# LEDBoard.net
KiCad netlist of a schematic drawn in EAGLE
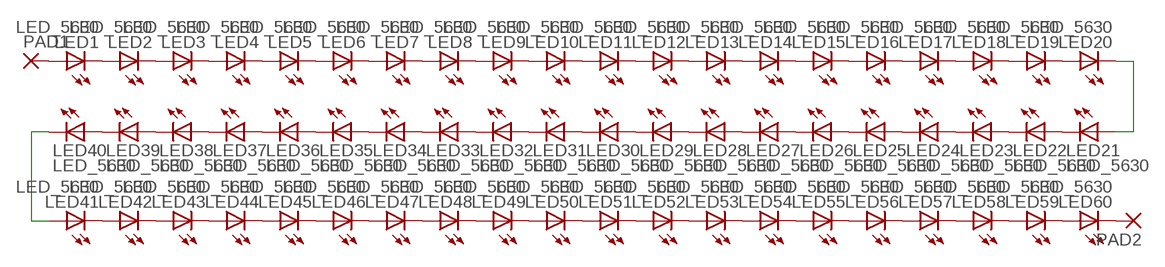
[diagram p0: schematic, sheet 1]

(export (version "E")
  (design (tool "Eeschema 10.0.6"))
  (components
    (comp (ref "LED1")
      (value "LED_5630")
      (footprint "eagle-import:LED5730")
      (libsource (lib "eagle-import") (part "LED_5630"))
    )
    (comp (ref "LED2")
      (value "LED_5630")
      (footprint "eagle-import:LED5730")
      (libsource (lib "eagle-import") (part "LED_5630"))
    )
    (comp (ref "LED3")
      (value "LED_5630")
      (footprint "eagle-import:LED5730")
      (libsource (lib "eagle-import") (part "LED_5630"))
    )
    (comp (ref "LED4")
      (value "LED_5630")
      (footprint "eagle-import:LED5730")
      (libsource (lib "eagle-import") (part "LED_5630"))
    )
    (comp (ref "LED5")
      (value "LED_5630")
      (footprint "eagle-import:LED5730")
      (libsource (lib "eagle-import") (part "LED_5630"))
    )
    (comp (ref "LED6")
      (value "LED_5630")
      (footprint "eagle-import:LED5730")
      (libsource (lib "eagle-import") (part "LED_5630"))
    )
    (comp (ref "LED7")
      (value "LED_5630")
      (footprint "eagle-import:LED5730")
      (libsource (lib "eagle-import") (part "LED_5630"))
    )
    (comp (ref "LED8")
      (value "LED_5630")
      (footprint "eagle-import:LED5730")
      (libsource (lib "eagle-import") (part "LED_5630"))
    )
    (comp (ref "LED9")
      (value "LED_5630")
      (footprint "eagle-import:LED5730")
      (libsource (lib "eagle-import") (part "LED_5630"))
    )
    (comp (ref "LED10")
      (value "LED_5630")
      (footprint "eagle-import:LED5730")
      (libsource (lib "eagle-import") (part "LED_5630"))
    )
    (comp (ref "LED11")
      (value "LED_5630")
      (footprint "eagle-import:LED5730")
      (libsource (lib "eagle-import") (part "LED_5630"))
    )
    (comp (ref "LED12")
      (value "LED_5630")
      (footprint "eagle-import:LED5730")
      (libsource (lib "eagle-import") (part "LED_5630"))
    )
    (comp (ref "LED13")
      (value "LED_5630")
      (footprint "eagle-import:LED5730")
      (libsource (lib "eagle-import") (part "LED_5630"))
    )
    (comp (ref "LED14")
      (value "LED_5630")
      (footprint "eagle-import:LED5730")
      (libsource (lib "eagle-import") (part "LED_5630"))
    )
    (comp (ref "LED15")
      (value "LED_5630")
      (footprint "eagle-import:LED5730")
      (libsource (lib "eagle-import") (part "LED_5630"))
    )
    (comp (ref "LED16")
      (value "LED_5630")
      (footprint "eagle-import:LED5730")
      (libsource (lib "eagle-import") (part "LED_5630"))
    )
    (comp (ref "LED17")
      (value "LED_5630")
      (footprint "eagle-import:LED5730")
      (libsource (lib "eagle-import") (part "LED_5630"))
    )
    (comp (ref "LED18")
      (value "LED_5630")
      (footprint "eagle-import:LED5730")
      (libsource (lib "eagle-import") (part "LED_5630"))
    )
    (comp (ref "LED19")
      (value "LED_5630")
      (footprint "eagle-import:LED5730")
      (libsource (lib "eagle-import") (part "LED_5630"))
    )
    (comp (ref "LED20")
      (value "LED_5630")
      (footprint "eagle-import:LED5730")
      (libsource (lib "eagle-import") (part "LED_5630"))
    )
    (comp (ref "LED21")
      (value "LED_5630")
      (footprint "eagle-import:LED5730")
      (libsource (lib "eagle-import") (part "LED_5630"))
    )
    (comp (ref "LED22")
      (value "LED_5630")
      (footprint "eagle-import:LED5730")
      (libsource (lib "eagle-import") (part "LED_5630"))
    )
    (comp (ref "LED23")
      (value "LED_5630")
      (footprint "eagle-import:LED5730")
      (libsource (lib "eagle-import") (part "LED_5630"))
    )
    (comp (ref "LED24")
      (value "LED_5630")
      (footprint "eagle-import:LED5730")
      (libsource (lib "eagle-import") (part "LED_5630"))
    )
    (comp (ref "LED25")
      (value "LED_5630")
      (footprint "eagle-import:LED5730")
      (libsource (lib "eagle-import") (part "LED_5630"))
    )
    (comp (ref "LED26")
      (value "LED_5630")
      (footprint "eagle-import:LED5730")
      (libsource (lib "eagle-import") (part "LED_5630"))
    )
    (comp (ref "LED27")
      (value "LED_5630")
      (footprint "eagle-import:LED5730")
      (libsource (lib "eagle-import") (part "LED_5630"))
    )
    (comp (ref "LED28")
      (value "LED_5630")
      (footprint "eagle-import:LED5730")
      (libsource (lib "eagle-import") (part "LED_5630"))
    )
    (comp (ref "LED29")
      (value "LED_5630")
      (footprint "eagle-import:LED5730")
      (libsource (lib "eagle-import") (part "LED_5630"))
    )
    (comp (ref "LED30")
      (value "LED_5630")
      (footprint "eagle-import:LED5730")
      (libsource (lib "eagle-import") (part "LED_5630"))
    )
    (comp (ref "LED31")
      (value "LED_5630")
      (footprint "eagle-import:LED5730")
      (libsource (lib "eagle-import") (part "LED_5630"))
    )
    (comp (ref "LED32")
      (value "LED_5630")
      (footprint "eagle-import:LED5730")
      (libsource (lib "eagle-import") (part "LED_5630"))
    )
    (comp (ref "LED33")
      (value "LED_5630")
      (footprint "eagle-import:LED5730")
      (libsource (lib "eagle-import") (part "LED_5630"))
    )
    (comp (ref "LED34")
      (value "LED_5630")
      (footprint "eagle-import:LED5730")
      (libsource (lib "eagle-import") (part "LED_5630"))
    )
    (comp (ref "LED35")
      (value "LED_5630")
      (footprint "eagle-import:LED5730")
      (libsource (lib "eagle-import") (part "LED_5630"))
    )
    (comp (ref "LED36")
      (value "LED_5630")
      (footprint "eagle-import:LED5730")
      (libsource (lib "eagle-import") (part "LED_5630"))
    )
    (comp (ref "LED37")
      (value "LED_5630")
      (footprint "eagle-import:LED5730")
      (libsource (lib "eagle-import") (part "LED_5630"))
    )
    (comp (ref "LED38")
      (value "LED_5630")
      (footprint "eagle-import:LED5730")
      (libsource (lib "eagle-import") (part "LED_5630"))
    )
    (comp (ref "LED39")
      (value "LED_5630")
      (footprint "eagle-import:LED5730")
      (libsource (lib "eagle-import") (part "LED_5630"))
    )
    (comp (ref "LED40")
      (value "LED_5630")
      (footprint "eagle-import:LED5730")
      (libsource (lib "eagle-import") (part "LED_5630"))
    )
    (comp (ref "LED41")
      (value "LED_5630")
      (footprint "eagle-import:LED5730")
      (libsource (lib "eagle-import") (part "LED_5630"))
    )
    (comp (ref "LED42")
      (value "LED_5630")
      (footprint "eagle-import:LED5730")
      (libsource (lib "eagle-import") (part "LED_5630"))
    )
    (comp (ref "LED43")
      (value "LED_5630")
      (footprint "eagle-import:LED5730")
      (libsource (lib "eagle-import") (part "LED_5630"))
    )
    (comp (ref "LED44")
      (value "LED_5630")
      (footprint "eagle-import:LED5730")
      (libsource (lib "eagle-import") (part "LED_5630"))
    )
    (comp (ref "LED45")
      (value "LED_5630")
      (footprint "eagle-import:LED5730")
      (libsource (lib "eagle-import") (part "LED_5630"))
    )
    (comp (ref "LED46")
      (value "LED_5630")
      (footprint "eagle-import:LED5730")
      (libsource (lib "eagle-import") (part "LED_5630"))
    )
    (comp (ref "LED47")
      (value "LED_5630")
      (footprint "eagle-import:LED5730")
      (libsource (lib "eagle-import") (part "LED_5630"))
    )
    (comp (ref "LED48")
      (value "LED_5630")
      (footprint "eagle-import:LED5730")
      (libsource (lib "eagle-import") (part "LED_5630"))
    )
    (comp (ref "LED49")
      (value "LED_5630")
      (footprint "eagle-import:LED5730")
      (libsource (lib "eagle-import") (part "LED_5630"))
    )
    (comp (ref "LED50")
      (value "LED_5630")
      (footprint "eagle-import:LED5730")
      (libsource (lib "eagle-import") (part "LED_5630"))
    )
    (comp (ref "LED51")
      (value "LED_5630")
      (footprint "eagle-import:LED5730")
      (libsource (lib "eagle-import") (part "LED_5630"))
    )
    (comp (ref "LED52")
      (value "LED_5630")
      (footprint "eagle-import:LED5730")
      (libsource (lib "eagle-import") (part "LED_5630"))
    )
    (comp (ref "LED53")
      (value "LED_5630")
      (footprint "eagle-import:LED5730")
      (libsource (lib "eagle-import") (part "LED_5630"))
    )
    (comp (ref "LED54")
      (value "LED_5630")
      (footprint "eagle-import:LED5730")
      (libsource (lib "eagle-import") (part "LED_5630"))
    )
    (comp (ref "LED55")
      (value "LED_5630")
      (footprint "eagle-import:LED5730")
      (libsource (lib "eagle-import") (part "LED_5630"))
    )
    (comp (ref "LED56")
      (value "LED_5630")
      (footprint "eagle-import:LED5730")
      (libsource (lib "eagle-import") (part "LED_5630"))
    )
    (comp (ref "LED57")
      (value "LED_5630")
      (footprint "eagle-import:LED5730")
      (libsource (lib "eagle-import") (part "LED_5630"))
    )
    (comp (ref "LED58")
      (value "LED_5630")
      (footprint "eagle-import:LED5730")
      (libsource (lib "eagle-import") (part "LED_5630"))
    )
    (comp (ref "LED59")
      (value "LED_5630")
      (footprint "eagle-import:LED5730")
      (libsource (lib "eagle-import") (part "LED_5630"))
    )
    (comp (ref "LED60")
      (value "LED_5630")
      (footprint "eagle-import:LED5730")
      (libsource (lib "eagle-import") (part "LED_5630"))
    )
    (comp (ref "PAD1")
      (value "SMD5")
      (footprint "eagle-import:SMD2,54-5,08")
      (libsource (lib "eagle-import") (part "SMD5"))
    )
    (comp (ref "PAD2")
      (value "SMD5")
      (footprint "eagle-import:SMD2,54-5,08")
      (libsource (lib "eagle-import") (part "SMD5"))
    )
  )
  (nets
    (net (code "1") (name "Net-(LED1-PadC)") (class "Default")
      (node (ref "LED1") (pin "C") (pinfunction "C_C") (pintype "passive"))
      (node (ref "LED2") (pin "A") (pinfunction "A_A") (pintype "passive"))
      (node (ref "LED2") (pin "A1") (pinfunction "A_A1") (pintype "passive"))
    )
    (net (code "2") (name "Net-(LED2-PadC)") (class "Default")
      (node (ref "LED2") (pin "C") (pinfunction "C_C") (pintype "passive"))
      (node (ref "LED3") (pin "A") (pinfunction "A_A") (pintype "passive"))
      (node (ref "LED3") (pin "A1") (pinfunction "A_A1") (pintype "passive"))
    )
    (net (code "3") (name "Net-(LED3-PadC)") (class "Default")
      (node (ref "LED3") (pin "C") (pinfunction "C_C") (pintype "passive"))
      (node (ref "LED4") (pin "A") (pinfunction "A_A") (pintype "passive"))
      (node (ref "LED4") (pin "A1") (pinfunction "A_A1") (pintype "passive"))
    )
    (net (code "4") (name "Net-(LED4-PadC)") (class "Default")
      (node (ref "LED4") (pin "C") (pinfunction "C_C") (pintype "passive"))
      (node (ref "LED5") (pin "A") (pinfunction "A_A") (pintype "passive"))
      (node (ref "LED5") (pin "A1") (pinfunction "A_A1") (pintype "passive"))
    )
    (net (code "5") (name "Net-(LED5-PadC)") (class "Default")
      (node (ref "LED5") (pin "C") (pinfunction "C_C") (pintype "passive"))
      (node (ref "LED6") (pin "A") (pinfunction "A_A") (pintype "passive"))
      (node (ref "LED6") (pin "A1") (pinfunction "A_A1") (pintype "passive"))
    )
    (net (code "6") (name "Net-(LED6-PadC)") (class "Default")
      (node (ref "LED6") (pin "C") (pinfunction "C_C") (pintype "passive"))
      (node (ref "LED7") (pin "A") (pinfunction "A_A") (pintype "passive"))
      (node (ref "LED7") (pin "A1") (pinfunction "A_A1") (pintype "passive"))
    )
    (net (code "7") (name "Net-(LED7-PadC)") (class "Default")
      (node (ref "LED7") (pin "C") (pinfunction "C_C") (pintype "passive"))
      (node (ref "LED8") (pin "A") (pinfunction "A_A") (pintype "passive"))
      (node (ref "LED8") (pin "A1") (pinfunction "A_A1") (pintype "passive"))
    )
    (net (code "8") (name "Net-(LED8-PadC)") (class "Default")
      (node (ref "LED8") (pin "C") (pinfunction "C_C") (pintype "passive"))
      (node (ref "LED9") (pin "A") (pinfunction "A_A") (pintype "passive"))
      (node (ref "LED9") (pin "A1") (pinfunction "A_A1") (pintype "passive"))
    )
    (net (code "9") (name "Net-(LED10-A-PadA1)") (class "Default")
      (node (ref "LED10") (pin "A") (pinfunction "A_A") (pintype "passive"))
      (node (ref "LED10") (pin "A1") (pinfunction "A_A1") (pintype "passive"))
      (node (ref "LED9") (pin "C") (pinfunction "C_C") (pintype "passive"))
    )
    (net (code "10") (name "Net-(LED10-PadC)") (class "Default")
      (node (ref "LED10") (pin "C") (pinfunction "C_C") (pintype "passive"))
      (node (ref "LED11") (pin "A") (pinfunction "A_A") (pintype "passive"))
      (node (ref "LED11") (pin "A1") (pinfunction "A_A1") (pintype "passive"))
    )
    (net (code "11") (name "Net-(LED11-PadC)") (class "Default")
      (node (ref "LED11") (pin "C") (pinfunction "C_C") (pintype "passive"))
      (node (ref "LED12") (pin "A") (pinfunction "A_A") (pintype "passive"))
      (node (ref "LED12") (pin "A1") (pinfunction "A_A1") (pintype "passive"))
    )
    (net (code "12") (name "Net-(LED12-PadC)") (class "Default")
      (node (ref "LED12") (pin "C") (pinfunction "C_C") (pintype "passive"))
      (node (ref "LED13") (pin "A") (pinfunction "A_A") (pintype "passive"))
      (node (ref "LED13") (pin "A1") (pinfunction "A_A1") (pintype "passive"))
    )
    (net (code "13") (name "Net-(LED13-PadC)") (class "Default")
      (node (ref "LED13") (pin "C") (pinfunction "C_C") (pintype "passive"))
      (node (ref "LED14") (pin "A") (pinfunction "A_A") (pintype "passive"))
      (node (ref "LED14") (pin "A1") (pinfunction "A_A1") (pintype "passive"))
    )
    (net (code "14") (name "Net-(LED14-PadC)") (class "Default")
      (node (ref "LED14") (pin "C") (pinfunction "C_C") (pintype "passive"))
      (node (ref "LED15") (pin "A") (pinfunction "A_A") (pintype "passive"))
      (node (ref "LED15") (pin "A1") (pinfunction "A_A1") (pintype "passive"))
    )
    (net (code "15") (name "Net-(LED15-PadC)") (class "Default")
      (node (ref "LED15") (pin "C") (pinfunction "C_C") (pintype "passive"))
      (node (ref "LED16") (pin "A") (pinfunction "A_A") (pintype "passive"))
      (node (ref "LED16") (pin "A1") (pinfunction "A_A1") (pintype "passive"))
    )
    (net (code "16") (name "Net-(LED16-PadC)") (class "Default")
      (node (ref "LED16") (pin "C") (pinfunction "C_C") (pintype "passive"))
      (node (ref "LED17") (pin "A") (pinfunction "A_A") (pintype "passive"))
      (node (ref "LED17") (pin "A1") (pinfunction "A_A1") (pintype "passive"))
    )
    (net (code "17") (name "Net-(LED17-PadC)") (class "Default")
      (node (ref "LED17") (pin "C") (pinfunction "C_C") (pintype "passive"))
      (node (ref "LED18") (pin "A") (pinfunction "A_A") (pintype "passive"))
      (node (ref "LED18") (pin "A1") (pinfunction "A_A1") (pintype "passive"))
    )
    (net (code "18") (name "Net-(LED18-PadC)") (class "Default")
      (node (ref "LED18") (pin "C") (pinfunction "C_C") (pintype "passive"))
      (node (ref "LED19") (pin "A") (pinfunction "A_A") (pintype "passive"))
      (node (ref "LED19") (pin "A1") (pinfunction "A_A1") (pintype "passive"))
    )
    (net (code "19") (name "Net-(LED19-PadC)") (class "Default")
      (node (ref "LED19") (pin "C") (pinfunction "C_C") (pintype "passive"))
      (node (ref "LED20") (pin "A") (pinfunction "A_A") (pintype "passive"))
      (node (ref "LED20") (pin "A1") (pinfunction "A_A1") (pintype "passive"))
    )
    (net (code "20") (name "Net-(LED20-PadC)") (class "Default")
      (node (ref "LED20") (pin "C") (pinfunction "C_C") (pintype "passive"))
      (node (ref "LED21") (pin "A") (pinfunction "A_A") (pintype "passive"))
      (node (ref "LED21") (pin "A1") (pinfunction "A_A1") (pintype "passive"))
    )
    (net (code "21") (name "Net-(LED21-PadC)") (class "Default")
      (node (ref "LED21") (pin "C") (pinfunction "C_C") (pintype "passive"))
      (node (ref "LED22") (pin "A") (pinfunction "A_A") (pintype "passive"))
      (node (ref "LED22") (pin "A1") (pinfunction "A_A1") (pintype "passive"))
    )
    (net (code "22") (name "Net-(LED22-PadC)") (class "Default")
      (node (ref "LED22") (pin "C") (pinfunction "C_C") (pintype "passive"))
      (node (ref "LED23") (pin "A") (pinfunction "A_A") (pintype "passive"))
      (node (ref "LED23") (pin "A1") (pinfunction "A_A1") (pintype "passive"))
    )
    (net (code "23") (name "Net-(LED23-PadC)") (class "Default")
      (node (ref "LED23") (pin "C") (pinfunction "C_C") (pintype "passive"))
      (node (ref "LED24") (pin "A") (pinfunction "A_A") (pintype "passive"))
      (node (ref "LED24") (pin "A1") (pinfunction "A_A1") (pintype "passive"))
    )
    (net (code "24") (name "Net-(LED24-PadC)") (class "Default")
      (node (ref "LED24") (pin "C") (pinfunction "C_C") (pintype "passive"))
      (node (ref "LED25") (pin "A") (pinfunction "A_A") (pintype "passive"))
      (node (ref "LED25") (pin "A1") (pinfunction "A_A1") (pintype "passive"))
    )
    (net (code "25") (name "Net-(LED25-PadC)") (class "Default")
      (node (ref "LED25") (pin "C") (pinfunction "C_C") (pintype "passive"))
      (node (ref "LED26") (pin "A") (pinfunction "A_A") (pintype "passive"))
      (node (ref "LED26") (pin "A1") (pinfunction "A_A1") (pintype "passive"))
    )
    (net (code "26") (name "Net-(LED26-PadC)") (class "Default")
      (node (ref "LED26") (pin "C") (pinfunction "C_C") (pintype "passive"))
      (node (ref "LED27") (pin "A") (pinfunction "A_A") (pintype "passive"))
      (node (ref "LED27") (pin "A1") (pinfunction "A_A1") (pintype "passive"))
    )
    (net (code "27") (name "Net-(LED27-PadC)") (class "Default")
      (node (ref "LED27") (pin "C") (pinfunction "C_C") (pintype "passive"))
      (node (ref "LED28") (pin "A") (pinfunction "A_A") (pintype "passive"))
      (node (ref "LED28") (pin "A1") (pinfunction "A_A1") (pintype "passive"))
    )
    (net (code "28") (name "Net-(LED28-PadC)") (class "Default")
      (node (ref "LED28") (pin "C") (pinfunction "C_C") (pintype "passive"))
      (node (ref "LED29") (pin "A") (pinfunction "A_A") (pintype "passive"))
      (node (ref "LED29") (pin "A1") (pinfunction "A_A1") (pintype "passive"))
    )
    (net (code "29") (name "Net-(LED29-PadC)") (class "Default")
      (node (ref "LED29") (pin "C") (pinfunction "C_C") (pintype "passive"))
      (node (ref "LED30") (pin "A") (pinfunction "A_A") (pintype "passive"))
      (node (ref "LED30") (pin "A1") (pinfunction "A_A1") (pintype "passive"))
    )
    (net (code "30") (name "Net-(LED30-PadC)") (class "Default")
      (node (ref "LED30") (pin "C") (pinfunction "C_C") (pintype "passive"))
      (node (ref "LED31") (pin "A") (pinfunction "A_A") (pintype "passive"))
      (node (ref "LED31") (pin "A1") (pinfunction "A_A1") (pintype "passive"))
    )
    (net (code "31") (name "Net-(LED31-PadC)") (class "Default")
      (node (ref "LED31") (pin "C") (pinfunction "C_C") (pintype "passive"))
      (node (ref "LED32") (pin "A") (pinfunction "A_A") (pintype "passive"))
      (node (ref "LED32") (pin "A1") (pinfunction "A_A1") (pintype "passive"))
    )
    (net (code "32") (name "Net-(LED32-PadC)") (class "Default")
      (node (ref "LED32") (pin "C") (pinfunction "C_C") (pintype "passive"))
      (node (ref "LED33") (pin "A") (pinfunction "A_A") (pintype "passive"))
      (node (ref "LED33") (pin "A1") (pinfunction "A_A1") (pintype "passive"))
    )
    (net (code "33") (name "Net-(LED33-PadC)") (class "Default")
      (node (ref "LED33") (pin "C") (pinfunction "C_C") (pintype "passive"))
      (node (ref "LED34") (pin "A") (pinfunction "A_A") (pintype "passive"))
      (node (ref "LED34") (pin "A1") (pinfunction "A_A1") (pintype "passive"))
    )
    (net (code "34") (name "Net-(LED34-PadC)") (class "Default")
      (node (ref "LED34") (pin "C") (pinfunction "C_C") (pintype "passive"))
      (node (ref "LED35") (pin "A") (pinfunction "A_A") (pintype "passive"))
      (node (ref "LED35") (pin "A1") (pinfunction "A_A1") (pintype "passive"))
    )
    (net (code "35") (name "Net-(LED35-PadC)") (class "Default")
      (node (ref "LED35") (pin "C") (pinfunction "C_C") (pintype "passive"))
      (node (ref "LED36") (pin "A") (pinfunction "A_A") (pintype "passive"))
      (node (ref "LED36") (pin "A1") (pinfunction "A_A1") (pintype "passive"))
    )
    (net (code "36") (name "Net-(LED36-PadC)") (class "Default")
      (node (ref "LED36") (pin "C") (pinfunction "C_C") (pintype "passive"))
      (node (ref "LED37") (pin "A") (pinfunction "A_A") (pintype "passive"))
      (node (ref "LED37") (pin "A1") (pinfunction "A_A1") (pintype "passive"))
    )
    (net (code "37") (name "Net-(LED37-PadC)") (class "Default")
      (node (ref "LED37") (pin "C") (pinfunction "C_C") (pintype "passive"))
      (node (ref "LED38") (pin "A") (pinfunction "A_A") (pintype "passive"))
      (node (ref "LED38") (pin "A1") (pinfunction "A_A1") (pintype "passive"))
    )
    (net (code "38") (name "Net-(LED38-PadC)") (class "Default")
      (node (ref "LED38") (pin "C") (pinfunction "C_C") (pintype "passive"))
      (node (ref "LED39") (pin "A") (pinfunction "A_A") (pintype "passive"))
      (node (ref "LED39") (pin "A1") (pinfunction "A_A1") (pintype "passive"))
    )
    (net (code "39") (name "Net-(LED39-PadC)") (class "Default")
      (node (ref "LED39") (pin "C") (pinfunction "C_C") (pintype "passive"))
      (node (ref "LED40") (pin "A") (pinfunction "A_A") (pintype "passive"))
      (node (ref "LED40") (pin "A1") (pinfunction "A_A1") (pintype "passive"))
    )
    (net (code "40") (name "Net-(LED40-PadC)") (class "Default")
      (node (ref "LED40") (pin "C") (pinfunction "C_C") (pintype "passive"))
      (node (ref "LED41") (pin "A") (pinfunction "A_A") (pintype "passive"))
      (node (ref "LED41") (pin "A1") (pinfunction "A_A1") (pintype "passive"))
    )
    (net (code "41") (name "Net-(LED41-PadC)") (class "Default")
      (node (ref "LED41") (pin "C") (pinfunction "C_C") (pintype "passive"))
      (node (ref "LED42") (pin "A") (pinfunction "A_A") (pintype "passive"))
      (node (ref "LED42") (pin "A1") (pinfunction "A_A1") (pintype "passive"))
    )
    (net (code "42") (name "Net-(LED42-PadC)") (class "Default")
      (node (ref "LED42") (pin "C") (pinfunction "C_C") (pintype "passive"))
      (node (ref "LED43") (pin "A") (pinfunction "A_A") (pintype "passive"))
      (node (ref "LED43") (pin "A1") (pinfunction "A_A1") (pintype "passive"))
    )
    (net (code "43") (name "Net-(LED43-PadC)") (class "Default")
      (node (ref "LED43") (pin "C") (pinfunction "C_C") (pintype "passive"))
      (node (ref "LED44") (pin "A") (pinfunction "A_A") (pintype "passive"))
      (node (ref "LED44") (pin "A1") (pinfunction "A_A1") (pintype "passive"))
    )
    (net (code "44") (name "Net-(LED44-PadC)") (class "Default")
      (node (ref "LED44") (pin "C") (pinfunction "C_C") (pintype "passive"))
      (node (ref "LED45") (pin "A") (pinfunction "A_A") (pintype "passive"))
      (node (ref "LED45") (pin "A1") (pinfunction "A_A1") (pintype "passive"))
    )
    (net (code "45") (name "Net-(LED45-PadC)") (class "Default")
      (node (ref "LED45") (pin "C") (pinfunction "C_C") (pintype "passive"))
      (node (ref "LED46") (pin "A") (pinfunction "A_A") (pintype "passive"))
      (node (ref "LED46") (pin "A1") (pinfunction "A_A1") (pintype "passive"))
    )
    (net (code "46") (name "Net-(LED46-PadC)") (class "Default")
      (node (ref "LED46") (pin "C") (pinfunction "C_C") (pintype "passive"))
      (node (ref "LED47") (pin "A") (pinfunction "A_A") (pintype "passive"))
      (node (ref "LED47") (pin "A1") (pinfunction "A_A1") (pintype "passive"))
    )
    (net (code "47") (name "Net-(LED47-PadC)") (class "Default")
      (node (ref "LED47") (pin "C") (pinfunction "C_C") (pintype "passive"))
      (node (ref "LED48") (pin "A") (pinfunction "A_A") (pintype "passive"))
      (node (ref "LED48") (pin "A1") (pinfunction "A_A1") (pintype "passive"))
    )
    (net (code "48") (name "Net-(LED48-PadC)") (class "Default")
      (node (ref "LED48") (pin "C") (pinfunction "C_C") (pintype "passive"))
      (node (ref "LED49") (pin "A") (pinfunction "A_A") (pintype "passive"))
      (node (ref "LED49") (pin "A1") (pinfunction "A_A1") (pintype "passive"))
    )
    (net (code "49") (name "Net-(LED49-PadC)") (class "Default")
      (node (ref "LED49") (pin "C") (pinfunction "C_C") (pintype "passive"))
      (node (ref "LED50") (pin "A") (pinfunction "A_A") (pintype "passive"))
      (node (ref "LED50") (pin "A1") (pinfunction "A_A1") (pintype "passive"))
    )
    (net (code "50") (name "Net-(LED50-PadC)") (class "Default")
      (node (ref "LED50") (pin "C") (pinfunction "C_C") (pintype "passive"))
      (node (ref "LED51") (pin "A") (pinfunction "A_A") (pintype "passive"))
      (node (ref "LED51") (pin "A1") (pinfunction "A_A1") (pintype "passive"))
    )
    (net (code "51") (name "Net-(LED51-PadC)") (class "Default")
      (node (ref "LED51") (pin "C") (pinfunction "C_C") (pintype "passive"))
      (node (ref "LED52") (pin "A") (pinfunction "A_A") (pintype "passive"))
      (node (ref "LED52") (pin "A1") (pinfunction "A_A1") (pintype "passive"))
    )
    (net (code "52") (name "Net-(LED52-PadC)") (class "Default")
      (node (ref "LED52") (pin "C") (pinfunction "C_C") (pintype "passive"))
      (node (ref "LED53") (pin "A") (pinfunction "A_A") (pintype "passive"))
      (node (ref "LED53") (pin "A1") (pinfunction "A_A1") (pintype "passive"))
    )
    (net (code "53") (name "Net-(LED53-PadC)") (class "Default")
      (node (ref "LED53") (pin "C") (pinfunction "C_C") (pintype "passive"))
      (node (ref "LED54") (pin "A") (pinfunction "A_A") (pintype "passive"))
      (node (ref "LED54") (pin "A1") (pinfunction "A_A1") (pintype "passive"))
    )
    (net (code "54") (name "Net-(LED54-PadC)") (class "Default")
      (node (ref "LED54") (pin "C") (pinfunction "C_C") (pintype "passive"))
      (node (ref "LED55") (pin "A") (pinfunction "A_A") (pintype "passive"))
      (node (ref "LED55") (pin "A1") (pinfunction "A_A1") (pintype "passive"))
    )
    (net (code "55") (name "Net-(LED55-PadC)") (class "Default")
      (node (ref "LED55") (pin "C") (pinfunction "C_C") (pintype "passive"))
      (node (ref "LED56") (pin "A") (pinfunction "A_A") (pintype "passive"))
      (node (ref "LED56") (pin "A1") (pinfunction "A_A1") (pintype "passive"))
    )
    (net (code "56") (name "Net-(LED56-PadC)") (class "Default")
      (node (ref "LED56") (pin "C") (pinfunction "C_C") (pintype "passive"))
      (node (ref "LED57") (pin "A") (pinfunction "A_A") (pintype "passive"))
      (node (ref "LED57") (pin "A1") (pinfunction "A_A1") (pintype "passive"))
    )
    (net (code "57") (name "Net-(LED57-PadC)") (class "Default")
      (node (ref "LED57") (pin "C") (pinfunction "C_C") (pintype "passive"))
      (node (ref "LED58") (pin "A") (pinfunction "A_A") (pintype "passive"))
      (node (ref "LED58") (pin "A1") (pinfunction "A_A1") (pintype "passive"))
    )
    (net (code "58") (name "Net-(LED58-PadC)") (class "Default")
      (node (ref "LED58") (pin "C") (pinfunction "C_C") (pintype "passive"))
      (node (ref "LED59") (pin "A") (pinfunction "A_A") (pintype "passive"))
      (node (ref "LED59") (pin "A1") (pinfunction "A_A1") (pintype "passive"))
    )
    (net (code "59") (name "Net-(LED59-PadC)") (class "Default")
      (node (ref "LED59") (pin "C") (pinfunction "C_C") (pintype "passive"))
      (node (ref "LED60") (pin "A") (pinfunction "A_A") (pintype "passive"))
      (node (ref "LED60") (pin "A1") (pinfunction "A_A1") (pintype "passive"))
    )
    (net (code "60") (name "Net-(PAD1-P)") (class "Default")
      (node (ref "LED1") (pin "A") (pinfunction "A_A") (pintype "passive"))
      (node (ref "LED1") (pin "A1") (pinfunction "A_A1") (pintype "passive"))
      (node (ref "PAD1") (pin "1") (pinfunction "P_1") (pintype "passive"))
    )
    (net (code "61") (name "Net-(PAD2-P)") (class "Default")
      (node (ref "LED60") (pin "C") (pinfunction "C_C") (pintype "passive"))
      (node (ref "PAD2") (pin "1") (pinfunction "P_1") (pintype "passive"))
    )
  )
)
